# activ_inductor.net
KiCad netlist of a schematic drawn in EAGLE
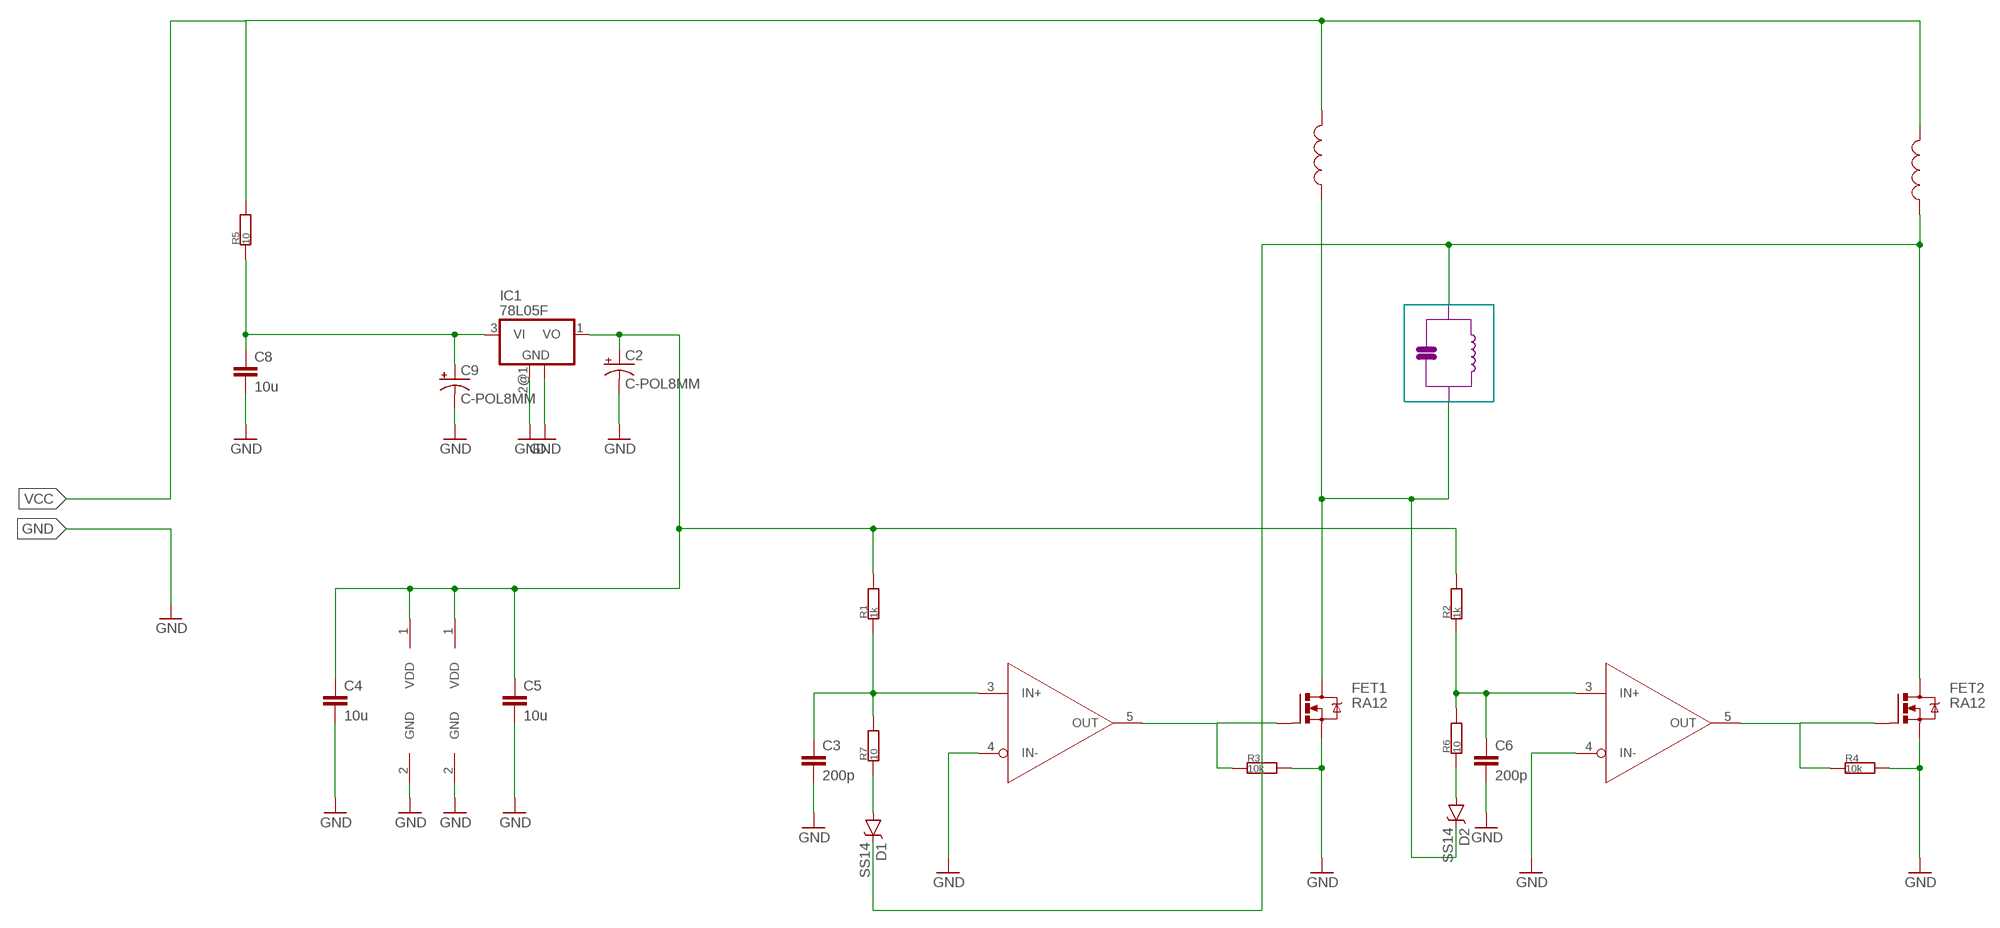
[diagram p0: schematic, sheet 1]

(export (version "E")
  (design (tool "Eeschema 10.0.6"))
  (components
    (comp (ref "C2")
      (value "C-POL8MM")
      (footprint "eagle-import:PCAP8")
      (libsource (lib "eagle-import") (part "C-POL8MM"))
    )
    (comp (ref "C3")
      (value "200p")
      (footprint "eagle-import:C0805")
      (libsource (lib "eagle-import") (part "CC0805"))
    )
    (comp (ref "C4")
      (value "10u")
      (footprint "eagle-import:C0805")
      (libsource (lib "eagle-import") (part "CC0805"))
    )
    (comp (ref "C5")
      (value "10u")
      (footprint "eagle-import:C0805")
      (libsource (lib "eagle-import") (part "CC0805"))
    )
    (comp (ref "C6")
      (value "200p")
      (footprint "eagle-import:C0805")
      (libsource (lib "eagle-import") (part "CC0805"))
    )
    (comp (ref "C8")
      (value "10u")
      (footprint "eagle-import:C0805")
      (libsource (lib "eagle-import") (part "CC0805"))
    )
    (comp (ref "C9")
      (value "C-POL8MM")
      (footprint "eagle-import:PCAP8")
      (libsource (lib "eagle-import") (part "C-POL8MM"))
    )
    (comp (ref "D1")
      (value "SS14")
      (footprint "eagle-import:SMA-DIODE")
      (libsource (lib "eagle-import") (part "SS14"))
    )
    (comp (ref "D2")
      (value "SS14")
      (footprint "eagle-import:SMA-DIODE")
      (libsource (lib "eagle-import") (part "SS14"))
    )
    (comp (ref "FET1")
      (value "RA12")
      (footprint "eagle-import:POWERPAK_SO8")
      (libsource (lib "eagle-import") (part "RA12"))
    )
    (comp (ref "FET2")
      (value "RA12")
      (footprint "eagle-import:POWERPAK_SO8")
      (libsource (lib "eagle-import") (part "RA12"))
    )
    (comp (ref "IC1")
      (value "78L05F")
      (footprint "eagle-import:SOT89")
      (libsource (lib "eagle-import") (part "78LF05"))
    )
    (comp (ref "R1")
      (value "1k")
      (footprint "eagle-import:R0805")
      (libsource (lib "eagle-import") (part "R0805"))
    )
    (comp (ref "R2")
      (value "1k")
      (footprint "eagle-import:R0805")
      (libsource (lib "eagle-import") (part "R0805"))
    )
    (comp (ref "R3")
      (value "10k")
      (footprint "eagle-import:R0805")
      (libsource (lib "eagle-import") (part "R0805"))
    )
    (comp (ref "R4")
      (value "10k")
      (footprint "eagle-import:R0805")
      (libsource (lib "eagle-import") (part "R0805"))
    )
    (comp (ref "R5")
      (value "10")
      (footprint "eagle-import:R1206")
      (libsource (lib "eagle-import") (part "R1206"))
    )
    (comp (ref "R6")
      (value "10")
      (footprint "eagle-import:R0805")
      (libsource (lib "eagle-import") (part "R0805"))
    )
    (comp (ref "R7")
      (value "10")
      (footprint "eagle-import:R0805")
      (libsource (lib "eagle-import") (part "R0805"))
    )
    (comp (ref "U$1")
      (value "FAN3100")
      (footprint "eagle-import:SOT23-5")
      (libsource (lib "eagle-import") (part "FAN3100"))
    )
    (comp (ref "U$2")
      (value "FAN3100")
      (footprint "eagle-import:SOT23-5")
      (libsource (lib "eagle-import") (part "FAN3100"))
    )
    (comp (ref "U$4")
      (value "INDUCTORRING_1")
      (footprint "eagle-import:INDUCTOR")
      (libsource (lib "eagle-import") (part "INDUCTORRING_1"))
    )
    (comp (ref "U$5")
      (value "INDUCTORRING_1")
      (footprint "eagle-import:INDUCTOR")
      (libsource (lib "eagle-import") (part "INDUCTORRING_1"))
    )
  )
  (nets
    (net (code "1") (name "GND") (class "Default")
      (node (ref "C2") (pin "P$2") (pinfunction "-_P$2") (pintype "passive"))
      (node (ref "C3") (pin "2") (pinfunction "2_2") (pintype "passive"))
      (node (ref "C4") (pin "2") (pinfunction "2_2") (pintype "passive"))
      (node (ref "C5") (pin "2") (pinfunction "2_2") (pintype "passive"))
      (node (ref "C6") (pin "2") (pinfunction "2_2") (pintype "passive"))
      (node (ref "C8") (pin "2") (pinfunction "2_2") (pintype "passive"))
      (node (ref "C9") (pin "P$2") (pinfunction "-_P$2") (pintype "passive"))
      (node (ref "FET1") (pin "1") (pinfunction "S_1") (pintype "passive"))
      (node (ref "FET1") (pin "2") (pinfunction "S_2") (pintype "passive"))
      (node (ref "FET1") (pin "3") (pinfunction "S_3") (pintype "passive"))
      (node (ref "FET2") (pin "1") (pinfunction "S_1") (pintype "passive"))
      (node (ref "FET2") (pin "2") (pinfunction "S_2") (pintype "passive"))
      (node (ref "FET2") (pin "3") (pinfunction "S_3") (pintype "passive"))
      (node (ref "IC1") (pin "2") (pinfunction "GND_2") (pintype "passive"))
      (node (ref "IC1") (pin "2@1") (pinfunction "GND_2@1") (pintype "passive"))
      (node (ref "R3") (pin "2") (pinfunction "2_2") (pintype "passive"))
      (node (ref "R4") (pin "2") (pinfunction "2_2") (pintype "passive"))
      (node (ref "U$1") (pin "2") (pinfunction "GND_2") (pintype "power_in"))
      (node (ref "U$1") (pin "4") (pinfunction "IN-_4") (pintype "bidirectional"))
      (node (ref "U$2") (pin "2") (pinfunction "GND_2") (pintype "power_in"))
      (node (ref "U$2") (pin "4") (pinfunction "IN-_4") (pintype "bidirectional"))
    )
    (net (code "2") (name "Net-(C2-+)") (class "Default")
      (node (ref "C2") (pin "P$1") (pinfunction "+_P$1") (pintype "passive"))
      (node (ref "C4") (pin "1") (pinfunction "1_1") (pintype "passive"))
      (node (ref "C5") (pin "1") (pinfunction "1_1") (pintype "passive"))
      (node (ref "IC1") (pin "1") (pinfunction "VO_1") (pintype "passive"))
      (node (ref "R1") (pin "2") (pinfunction "2_2") (pintype "passive"))
      (node (ref "R2") (pin "2") (pinfunction "2_2") (pintype "passive"))
      (node (ref "U$1") (pin "1") (pinfunction "VDD_1") (pintype "power_in"))
      (node (ref "U$2") (pin "1") (pinfunction "VDD_1") (pintype "power_in"))
    )
    (net (code "3") (name "Net-(C9-+)") (class "Default")
      (node (ref "C8") (pin "1") (pinfunction "1_1") (pintype "passive"))
      (node (ref "C9") (pin "P$1") (pinfunction "+_P$1") (pintype "passive"))
      (node (ref "IC1") (pin "3") (pinfunction "VI_3") (pintype "input"))
      (node (ref "R5") (pin "1") (pinfunction "1_1") (pintype "passive"))
    )
    (net (code "4") (name "Net-(D1-PadA)") (class "Default")
      (node (ref "D1") (pin "A") (pinfunction "A_A") (pintype "passive"))
      (node (ref "R7") (pin "1") (pinfunction "1_1") (pintype "passive"))
    )
    (net (code "5") (name "Net-(D2-PadA)") (class "Default")
      (node (ref "D2") (pin "A") (pinfunction "A_A") (pintype "passive"))
      (node (ref "R6") (pin "1") (pinfunction "1_1") (pintype "passive"))
    )
    (net (code "6") (name "Net-(FET1-G)") (class "Default")
      (node (ref "FET1") (pin "4") (pinfunction "G_4") (pintype "passive"))
      (node (ref "R3") (pin "1") (pinfunction "1_1") (pintype "passive"))
      (node (ref "U$1") (pin "5") (pinfunction "OUT_5") (pintype "bidirectional"))
    )
    (net (code "7") (name "Net-(FET2-G)") (class "Default")
      (node (ref "FET2") (pin "4") (pinfunction "G_4") (pintype "passive"))
      (node (ref "R4") (pin "1") (pinfunction "1_1") (pintype "passive"))
      (node (ref "U$2") (pin "5") (pinfunction "OUT_5") (pintype "bidirectional"))
    )
    (net (code "8") (name "Net-(U$1A-IN+)") (class "Default")
      (node (ref "C3") (pin "1") (pinfunction "1_1") (pintype "passive"))
      (node (ref "R1") (pin "1") (pinfunction "1_1") (pintype "passive"))
      (node (ref "R7") (pin "2") (pinfunction "2_2") (pintype "passive"))
      (node (ref "U$1") (pin "3") (pinfunction "IN+_3") (pintype "bidirectional"))
    )
    (net (code "9") (name "Net-(U$2A-IN+)") (class "Default")
      (node (ref "C6") (pin "1") (pinfunction "1_1") (pintype "passive"))
      (node (ref "R2") (pin "1") (pinfunction "1_1") (pintype "passive"))
      (node (ref "R6") (pin "2") (pinfunction "2_2") (pintype "passive"))
      (node (ref "U$2") (pin "3") (pinfunction "IN+_3") (pintype "bidirectional"))
    )
    (net (code "10") (name "Net-(U$4-P$1)") (class "Default")
      (node (ref "D1") (pin "C") (pinfunction "C_C") (pintype "passive"))
      (node (ref "FET2") (pin "5") (pinfunction "D_5") (pintype "passive"))
      (node (ref "FET2") (pin "6") (pinfunction "D_6") (pintype "passive"))
      (node (ref "FET2") (pin "7") (pinfunction "D_7") (pintype "passive"))
      (node (ref "FET2") (pin "8") (pinfunction "D_8") (pintype "passive"))
      (node (ref "FET2") (pin "P$1") (pinfunction "D_P$1") (pintype "passive"))
      (node (ref "U$4") (pin "1") (pinfunction "P$1_1") (pintype "power_in"))
    )
    (net (code "11") (name "Net-(U$5-P$1)") (class "Default")
      (node (ref "D2") (pin "C") (pinfunction "C_C") (pintype "passive"))
      (node (ref "FET1") (pin "5") (pinfunction "D_5") (pintype "passive"))
      (node (ref "FET1") (pin "6") (pinfunction "D_6") (pintype "passive"))
      (node (ref "FET1") (pin "7") (pinfunction "D_7") (pintype "passive"))
      (node (ref "FET1") (pin "8") (pinfunction "D_8") (pintype "passive"))
      (node (ref "FET1") (pin "P$1") (pinfunction "D_P$1") (pintype "passive"))
      (node (ref "U$5") (pin "1") (pinfunction "P$1_1") (pintype "power_in"))
    )
    (net (code "12") (name "VCC") (class "Default")
      (node (ref "R5") (pin "2") (pinfunction "2_2") (pintype "passive"))
      (node (ref "U$4") (pin "2") (pinfunction "P$2_2") (pintype "bidirectional"))
      (node (ref "U$5") (pin "2") (pinfunction "P$2_2") (pintype "bidirectional"))
    )
  )
)
